# LPC800_TSSOP_breadboard.net
KiCad netlist of a schematic drawn in EAGLE
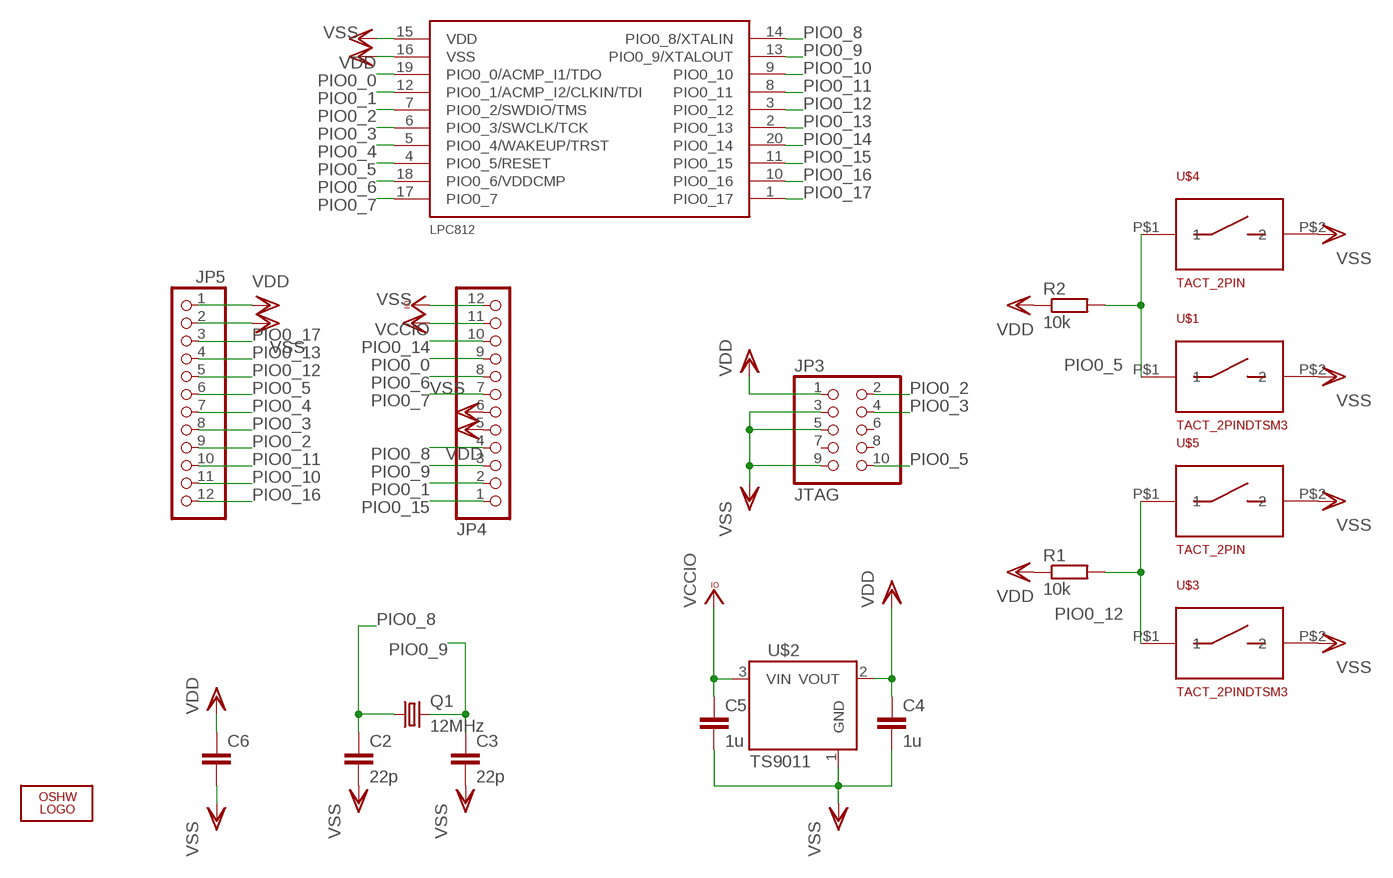
[diagram p0: schematic, sheet 1]

(export (version "E")
  (design (tool "Eeschema 10.0.6"))
  (components
    (comp (ref "C2")
      (value "22p")
      (footprint "eagle-import:C0603K")
      (libsource (lib "eagle-import") (part "C-EUC0603K"))
    )
    (comp (ref "C3")
      (value "22p")
      (footprint "eagle-import:C0603K")
      (libsource (lib "eagle-import") (part "C-EUC0603K"))
    )
    (comp (ref "C4")
      (value "1u")
      (footprint "eagle-import:C0805K")
      (libsource (lib "eagle-import") (part "bart_rcl_C-EUC0805K"))
    )
    (comp (ref "C5")
      (value "1u")
      (footprint "eagle-import:C0805K")
      (libsource (lib "eagle-import") (part "bart_rcl_C-EUC0805K"))
    )
    (comp (ref "C6")
      (value "C-EUC0603K")
      (footprint "eagle-import:C0603K")
      (libsource (lib "eagle-import") (part "C-EUC0603K"))
    )
    (comp (ref "JP3")
      (value "JTAG")
      (footprint "eagle-import:2X05_1.27_SMD")
      (libsource (lib "eagle-import") (part "PINHD-2X5SMD_1.27_SMD"))
    )
    (comp (ref "JP4")
      (value "PINHD-1X12NORM_OCT")
      (footprint "eagle-import:1X12_NORMAL_OCT")
      (libsource (lib "eagle-import") (part "PINHD-1X12NORM_OCT"))
    )
    (comp (ref "JP5")
      (value "PINHD-1X12NORM_OCT")
      (footprint "eagle-import:1X12_NORMAL_OCT")
      (libsource (lib "eagle-import") (part "PINHD-1X12NORM_OCT"))
    )
    (comp (ref "LOGO2")
      (value "OSHW_LOGO_FILLX0150-NT")
      (footprint "eagle-import:OSHW_FILLX150_NOTEXT")
      (libsource (lib "eagle-import") (part "OSHW_LOGO_FILLX0150-NT"))
    )
    (comp (ref "LPC812")
      (value "LPC812M101JDH20")
      (footprint "eagle-import:TSSOP20")
      (libsource (lib "eagle-import") (part "LPC812M101JDH20"))
    )
    (comp (ref "Q1")
      (value "12MHz")
      (footprint "eagle-import:CRYSTAL_5.0X3.2")
      (libsource (lib "eagle-import") (part "CRYSTALSMD_5.0X3.2"))
    )
    (comp (ref "R1")
      (value "10k")
      (footprint "eagle-import:R0603")
      (libsource (lib "eagle-import") (part "R-EU_R0603"))
    )
    (comp (ref "R2")
      (value "10k")
      (footprint "eagle-import:R0603")
      (libsource (lib "eagle-import") (part "R-EU_R0603"))
    )
    (comp (ref "U$1")
      (value "TACT_2PINDTSM3")
      (footprint "eagle-import:DTSM3")
      (libsource (lib "eagle-import") (part "TACT_2PINDTSM3"))
    )
    (comp (ref "U$2")
      (value "TS9011")
      (footprint "eagle-import:SOT23-3")
      (libsource (lib "eagle-import") (part "TS9011"))
    )
    (comp (ref "U$3")
      (value "TACT_2PINDTSM3")
      (footprint "eagle-import:DTSM3")
      (libsource (lib "eagle-import") (part "TACT_2PINDTSM3"))
    )
    (comp (ref "U$4")
      (value "TACT_2PIN")
      (footprint "eagle-import:TD-85XU")
      (libsource (lib "eagle-import") (part "TACT_2PIN"))
    )
    (comp (ref "U$5")
      (value "TACT_2PIN")
      (footprint "eagle-import:TD-85XU")
      (libsource (lib "eagle-import") (part "TACT_2PIN"))
    )
  )
  (nets
    (net (code "1") (name "/PIO0_0") (class "Default")
      (node (ref "JP4") (pin "9") (pinfunction "9_9") (pintype "passive"))
      (node (ref "LPC812") (pin "19") (pinfunction "PIO0_0/ACMP_I1/TDO_19") (pintype "bidirectional"))
    )
    (net (code "2") (name "/PIO0_1") (class "Default")
      (node (ref "JP4") (pin "2") (pinfunction "2_2") (pintype "passive"))
      (node (ref "LPC812") (pin "12") (pinfunction "PIO0_1/ACMP_I2/CLKIN/TDI_12") (pintype "bidirectional"))
    )
    (net (code "3") (name "/PIO0_2") (class "Default")
      (node (ref "JP3") (pin "2") (pinfunction "2_2") (pintype "passive"))
      (node (ref "JP5") (pin "9") (pinfunction "9_9") (pintype "passive"))
      (node (ref "LPC812") (pin "7") (pinfunction "PIO0_2/SWDIO/TMS_7") (pintype "bidirectional"))
    )
    (net (code "4") (name "/PIO0_3") (class "Default")
      (node (ref "JP3") (pin "4") (pinfunction "4_4") (pintype "passive"))
      (node (ref "JP5") (pin "8") (pinfunction "8_8") (pintype "passive"))
      (node (ref "LPC812") (pin "6") (pinfunction "PIO0_3/SWCLK/TCK_6") (pintype "bidirectional"))
    )
    (net (code "5") (name "/PIO0_4") (class "Default")
      (node (ref "JP5") (pin "7") (pinfunction "7_7") (pintype "passive"))
      (node (ref "LPC812") (pin "5") (pinfunction "PIO0_4/WAKEUP/TRST_5") (pintype "bidirectional"))
    )
    (net (code "6") (name "/PIO0_5") (class "Default")
      (node (ref "JP3") (pin "10") (pinfunction "10_10") (pintype "passive"))
      (node (ref "JP5") (pin "6") (pinfunction "6_6") (pintype "passive"))
      (node (ref "LPC812") (pin "4") (pinfunction "PIO0_5/RESET_4") (pintype "bidirectional"))
      (node (ref "R2") (pin "2") (pinfunction "2_2") (pintype "passive"))
      (node (ref "U$1") (pin "P$1") (pinfunction "1_P$1") (pintype "bidirectional"))
      (node (ref "U$4") (pin "P$1") (pinfunction "1_P$1") (pintype "bidirectional"))
    )
    (net (code "7") (name "/PIO0_6") (class "Default")
      (node (ref "JP4") (pin "8") (pinfunction "8_8") (pintype "passive"))
      (node (ref "LPC812") (pin "18") (pinfunction "PIO0_6/VDDCMP_18") (pintype "bidirectional"))
    )
    (net (code "8") (name "/PIO0_7") (class "Default")
      (node (ref "JP4") (pin "7") (pinfunction "7_7") (pintype "passive"))
      (node (ref "LPC812") (pin "17") (pinfunction "PIO0_7_17") (pintype "bidirectional"))
    )
    (net (code "9") (name "/PIO0_8") (class "Default")
      (node (ref "C2") (pin "1") (pinfunction "1_1") (pintype "passive"))
      (node (ref "JP4") (pin "4") (pinfunction "4_4") (pintype "passive"))
      (node (ref "LPC812") (pin "14") (pinfunction "PIO0_8/XTALIN_14") (pintype "bidirectional"))
      (node (ref "Q1") (pin "1") (pinfunction "1_1") (pintype "passive"))
    )
    (net (code "10") (name "/PIO0_9") (class "Default")
      (node (ref "C3") (pin "1") (pinfunction "1_1") (pintype "passive"))
      (node (ref "JP4") (pin "3") (pinfunction "3_3") (pintype "passive"))
      (node (ref "LPC812") (pin "13") (pinfunction "PIO0_9/XTALOUT_13") (pintype "bidirectional"))
      (node (ref "Q1") (pin "2") (pinfunction "2_2") (pintype "passive"))
    )
    (net (code "11") (name "/PIO0_10") (class "Default")
      (node (ref "JP5") (pin "11") (pinfunction "11_11") (pintype "passive"))
      (node (ref "LPC812") (pin "9") (pinfunction "PIO0_10_9") (pintype "bidirectional"))
    )
    (net (code "12") (name "/PIO0_11") (class "Default")
      (node (ref "JP5") (pin "10") (pinfunction "10_10") (pintype "passive"))
      (node (ref "LPC812") (pin "8") (pinfunction "PIO0_11_8") (pintype "bidirectional"))
    )
    (net (code "13") (name "/PIO0_12") (class "Default")
      (node (ref "JP5") (pin "5") (pinfunction "5_5") (pintype "passive"))
      (node (ref "LPC812") (pin "3") (pinfunction "PIO0_12_3") (pintype "bidirectional"))
      (node (ref "R1") (pin "2") (pinfunction "2_2") (pintype "passive"))
      (node (ref "U$3") (pin "P$1") (pinfunction "1_P$1") (pintype "bidirectional"))
      (node (ref "U$5") (pin "P$1") (pinfunction "1_P$1") (pintype "bidirectional"))
    )
    (net (code "14") (name "/PIO0_13") (class "Default")
      (node (ref "JP5") (pin "4") (pinfunction "4_4") (pintype "passive"))
      (node (ref "LPC812") (pin "2") (pinfunction "PIO0_13_2") (pintype "bidirectional"))
    )
    (net (code "15") (name "/PIO0_14") (class "Default")
      (node (ref "JP4") (pin "10") (pinfunction "10_10") (pintype "passive"))
      (node (ref "LPC812") (pin "20") (pinfunction "PIO0_14_20") (pintype "bidirectional"))
    )
    (net (code "16") (name "/PIO0_15") (class "Default")
      (node (ref "JP4") (pin "1") (pinfunction "1_1") (pintype "passive"))
      (node (ref "LPC812") (pin "11") (pinfunction "PIO0_15_11") (pintype "bidirectional"))
    )
    (net (code "17") (name "/PIO0_16") (class "Default")
      (node (ref "JP5") (pin "12") (pinfunction "12_12") (pintype "passive"))
      (node (ref "LPC812") (pin "10") (pinfunction "PIO0_16_10") (pintype "bidirectional"))
    )
    (net (code "18") (name "/PIO0_17") (class "Default")
      (node (ref "JP5") (pin "3") (pinfunction "3_3") (pintype "passive"))
      (node (ref "LPC812") (pin "1") (pinfunction "PIO0_17_1") (pintype "bidirectional"))
    )
    (net (code "19") (name "VCCIO") (class "Default")
      (node (ref "C5") (pin "1") (pinfunction "1_1") (pintype "passive"))
      (node (ref "JP4") (pin "12") (pinfunction "12_12") (pintype "passive"))
      (node (ref "U$2") (pin "3") (pinfunction "VIN_3") (pintype "bidirectional"))
    )
    (net (code "20") (name "VDD") (class "Default")
      (node (ref "C4") (pin "1") (pinfunction "1_1") (pintype "passive"))
      (node (ref "C6") (pin "1") (pinfunction "1_1") (pintype "passive"))
      (node (ref "JP3") (pin "1") (pinfunction "1_1") (pintype "passive"))
      (node (ref "JP4") (pin "5") (pinfunction "5_5") (pintype "passive"))
      (node (ref "JP5") (pin "1") (pinfunction "1_1") (pintype "passive"))
      (node (ref "LPC812") (pin "15") (pinfunction "VDD_15") (pintype "bidirectional"))
      (node (ref "R1") (pin "1") (pinfunction "1_1") (pintype "passive"))
      (node (ref "R2") (pin "1") (pinfunction "1_1") (pintype "passive"))
      (node (ref "U$2") (pin "2") (pinfunction "VOUT_2") (pintype "bidirectional"))
    )
    (net (code "21") (name "VSS") (class "Default")
      (node (ref "C2") (pin "2") (pinfunction "2_2") (pintype "passive"))
      (node (ref "C3") (pin "2") (pinfunction "2_2") (pintype "passive"))
      (node (ref "C4") (pin "2") (pinfunction "2_2") (pintype "passive"))
      (node (ref "C5") (pin "2") (pinfunction "2_2") (pintype "passive"))
      (node (ref "C6") (pin "2") (pinfunction "2_2") (pintype "passive"))
      (node (ref "JP3") (pin "3") (pinfunction "3_3") (pintype "passive"))
      (node (ref "JP3") (pin "5") (pinfunction "5_5") (pintype "passive"))
      (node (ref "JP3") (pin "9") (pinfunction "9_9") (pintype "passive"))
      (node (ref "JP4") (pin "11") (pinfunction "11_11") (pintype "passive"))
      (node (ref "JP4") (pin "6") (pinfunction "6_6") (pintype "passive"))
      (node (ref "JP5") (pin "2") (pinfunction "2_2") (pintype "passive"))
      (node (ref "LPC812") (pin "16") (pinfunction "VSS_16") (pintype "bidirectional"))
      (node (ref "U$1") (pin "P$2") (pinfunction "2_P$2") (pintype "bidirectional"))
      (node (ref "U$2") (pin "1") (pinfunction "GND_1") (pintype "bidirectional"))
      (node (ref "U$3") (pin "P$2") (pinfunction "2_P$2") (pintype "bidirectional"))
      (node (ref "U$4") (pin "P$2") (pinfunction "2_P$2") (pintype "bidirectional"))
      (node (ref "U$5") (pin "P$2") (pinfunction "2_P$2") (pintype "bidirectional"))
    )
    (net (code "22") (name "unconnected-(JP3-Pad6)") (class "Default")
      (node (ref "JP3") (pin "6") (pinfunction "6_6") (pintype "passive"))
    )
    (net (code "23") (name "unconnected-(JP3-Pad7)") (class "Default")
      (node (ref "JP3") (pin "7") (pinfunction "7_7") (pintype "passive"))
    )
    (net (code "24") (name "unconnected-(JP3-Pad8)") (class "Default")
      (node (ref "JP3") (pin "8") (pinfunction "8_8") (pintype "passive"))
    )
  )
)
